# ESP32CAM-Enclosure.net
KiCad netlist of a schematic drawn in EAGLE
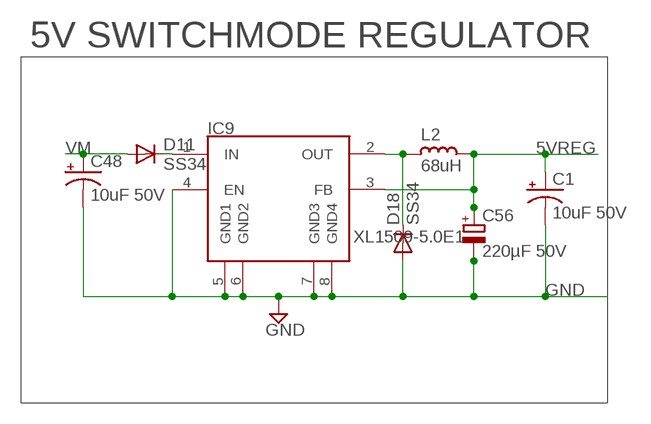
[diagram p0: schematic, sheet 1]

(export (version "E")
  (design (tool "Eeschema 10.0.6"))
  (components
    (comp (ref "C1")
      (value "10uF 50V")
      (footprint "eagle-import:EIA3216")
      (libsource (lib "eagle-import") (part "CAP_POL1206"))
    )
    (comp (ref "C48")
      (value "10uF 50V")
      (footprint "eagle-import:EIA3216")
      (libsource (lib "eagle-import") (part "CAP_POL1206"))
    )
    (comp (ref "C56")
      (value "220µF 50V")
      (footprint "eagle-import:E3,5-10")
      (libsource (lib "eagle-import") (part "CPOL-EUE3.5-10"))
    )
    (comp (ref "D11")
      (value "SS34")
      (footprint "eagle-import:DO-214AC")
      (libsource (lib "eagle-import") (part "DIODE-DO-214AC"))
    )
    (comp (ref "D18")
      (value "SS34")
      (footprint "eagle-import:DO-214AC")
      (libsource (lib "eagle-import") (part "DIODE-DO-214AC"))
    )
    (comp (ref "IC9")
      (value "XL1509-5.0E1")
      (footprint "eagle-import:SO08")
      (libsource (lib "eagle-import") (part "XL1509"))
    )
    (comp (ref "L2")
      (value "68uH")
      (footprint "eagle-import:CD75")
      (libsource (lib "eagle-import") (part "L_CD75"))
    )
  )
  (nets
    (net (code "1") (name "/5VREG") (class "Default")
      (node (ref "C1") (pin "A") (pinfunction "+_A") (pintype "passive"))
      (node (ref "C56") (pin "+") (pinfunction "+_+") (pintype "passive"))
      (node (ref "IC9") (pin "3") (pinfunction "FB_3") (pintype "bidirectional"))
      (node (ref "L2") (pin "1") (pinfunction "1_1") (pintype "passive"))
    )
    (net (code "2") (name "/VM") (class "Default")
      (node (ref "C48") (pin "A") (pinfunction "+_A") (pintype "passive"))
      (node (ref "D11") (pin "2") (pinfunction "A_2") (pintype "passive"))
    )
    (net (code "3") (name "GND") (class "Default")
      (node (ref "C1") (pin "C") (pinfunction "-_C") (pintype "passive"))
      (node (ref "C48") (pin "C") (pinfunction "-_C") (pintype "passive"))
      (node (ref "C56") (pin "-") (pinfunction "-_-") (pintype "passive"))
      (node (ref "D18") (pin "2") (pinfunction "A_2") (pintype "passive"))
      (node (ref "IC9") (pin "4") (pinfunction "EN_4") (pintype "bidirectional"))
      (node (ref "IC9") (pin "5") (pinfunction "GND1_5") (pintype "bidirectional"))
      (node (ref "IC9") (pin "6") (pinfunction "GND2_6") (pintype "bidirectional"))
      (node (ref "IC9") (pin "7") (pinfunction "GND3_7") (pintype "bidirectional"))
      (node (ref "IC9") (pin "8") (pinfunction "GND4_8") (pintype "bidirectional"))
    )
    (net (code "4") (name "Net-(D11-C)") (class "Default")
      (node (ref "D11") (pin "1") (pinfunction "C_1") (pintype "passive"))
      (node (ref "IC9") (pin "1") (pinfunction "IN_1") (pintype "bidirectional"))
    )
    (net (code "5") (name "Net-(D18-C)") (class "Default")
      (node (ref "D18") (pin "1") (pinfunction "C_1") (pintype "passive"))
      (node (ref "IC9") (pin "2") (pinfunction "OUT_2") (pintype "bidirectional"))
      (node (ref "L2") (pin "2") (pinfunction "2_2") (pintype "passive"))
    )
  )
)
